# Flyback_Transformer.net
KiCad netlist of a schematic drawn in Altium Designer
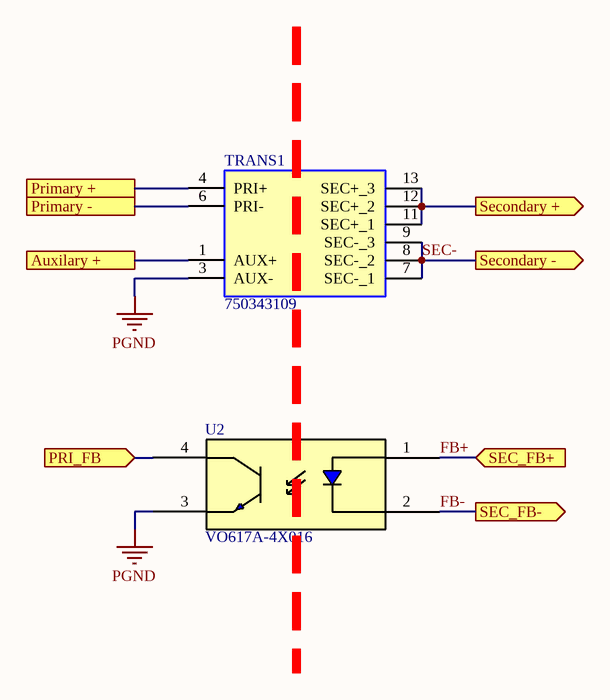
[diagram p0: Flyback Transformer.SchDoc]

(export (version "E")
  (design (tool "Eeschema 10.0.6"))
  (components
    (comp (ref "TRANS1")
      (value "750343109")
      (footprint "750343109")
      (description "Power Transformers WE-FB SMD Flyback Dialog Semi iW1830")
      (libsource (lib "SMPS Schlib") (part "750343109"))
    )
    (comp (ref "U2")
      (value "VO617A-4X016")
      (footprint "VO617A-4X016")
      (description "Transistor Output Optocouplers RECOMMENDED ALT 782-SFH617A-4X016")
      (libsource (lib "SMPS Schlib") (part "VO617A-4X016"))
    )
  )
  (nets
    (net (code "1") (name "/Auxilary +") (class "Default")
      (node (ref "TRANS1") (pin "1") (pinfunction "AUX+_1") (pintype "passive"))
    )
    (net (code "2") (name "/FB+") (class "Default")
      (node (ref "U2") (pin "1") (pinfunction "A_1") (pintype "passive"))
    )
    (net (code "3") (name "/FB-") (class "Default")
      (node (ref "U2") (pin "2") (pinfunction "C_2") (pintype "passive"))
    )
    (net (code "4") (name "/PRI_FB") (class "Default")
      (node (ref "U2") (pin "4") (pinfunction "C_4") (pintype "passive"))
    )
    (net (code "5") (name "/Primary +") (class "Default")
      (node (ref "TRANS1") (pin "4") (pinfunction "PRI+_4") (pintype "passive"))
    )
    (net (code "6") (name "/Primary -") (class "Default")
      (node (ref "TRANS1") (pin "6") (pinfunction "PRI-_6") (pintype "passive"))
    )
    (net (code "7") (name "/SEC-") (class "Default")
      (node (ref "TRANS1") (pin "7") (pinfunction "SEC-_1_7") (pintype "passive"))
      (node (ref "TRANS1") (pin "8") (pinfunction "SEC-_2_8") (pintype "passive"))
      (node (ref "TRANS1") (pin "9") (pinfunction "SEC-_3_9") (pintype "passive"))
    )
    (net (code "8") (name "/Secondary +") (class "Default")
      (node (ref "TRANS1") (pin "11") (pinfunction "SEC+_1_11") (pintype "passive"))
      (node (ref "TRANS1") (pin "12") (pinfunction "SEC+_2_12") (pintype "passive"))
      (node (ref "TRANS1") (pin "13") (pinfunction "SEC+_3_13") (pintype "passive"))
    )
    (net (code "9") (name "PGND") (class "Default")
      (node (ref "TRANS1") (pin "3") (pinfunction "AUX-_3") (pintype "passive"))
      (node (ref "U2") (pin "3") (pinfunction "E_3") (pintype "passive"))
    )
  )
)
